# ADB-3020-CDV.net
KiCad netlist of a schematic drawn in EAGLE
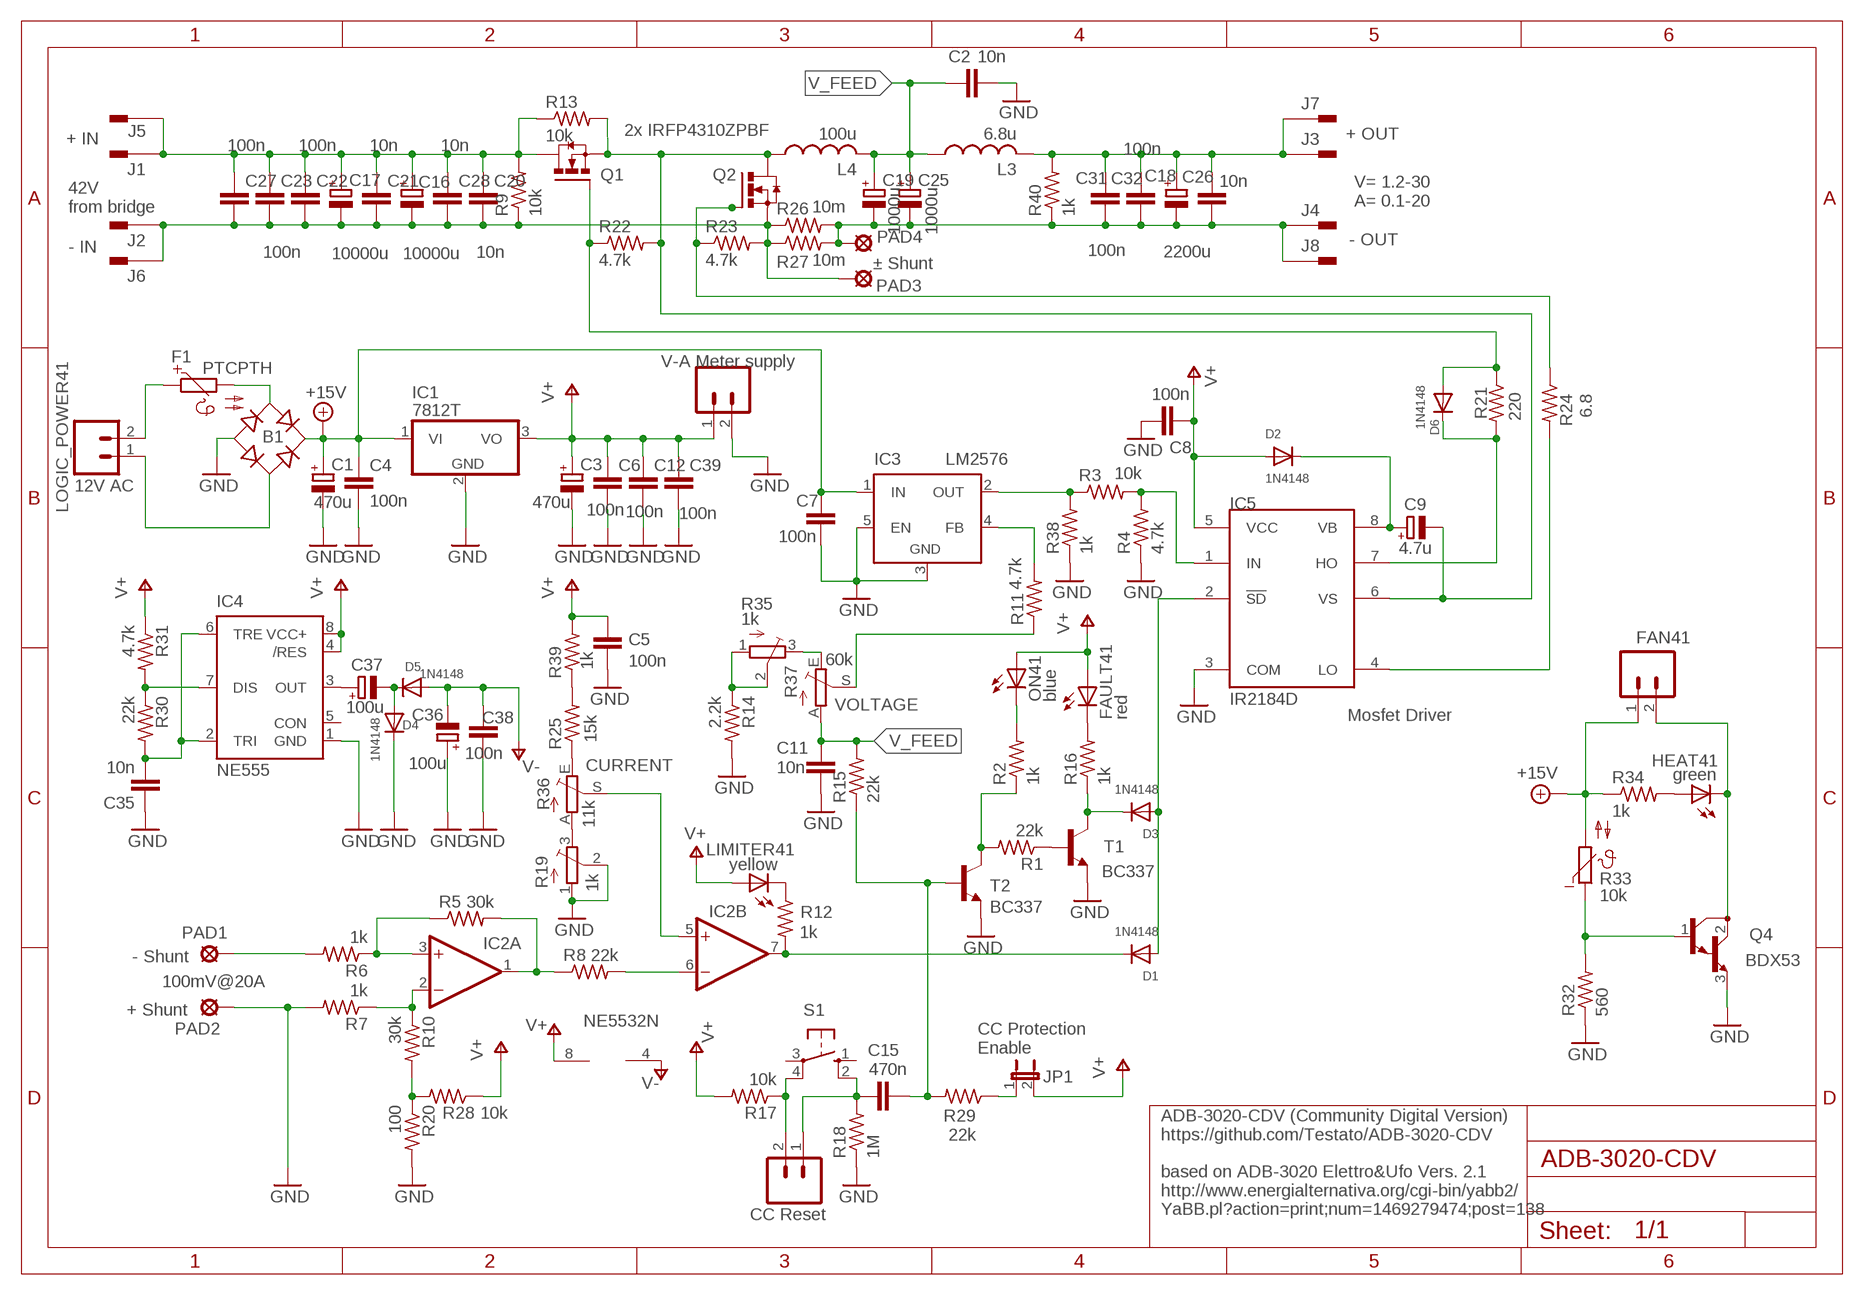
[diagram p0: schematic, sheet 1]

(export (version "E")
  (design (tool "Eeschema 10.0.6"))
  (components
    (comp (ref "B1")
      (value "RECTIFIER-RB1A")
      (footprint "eagle-import:RB1A")
      (libsource (lib "eagle-import") (part "RECTIFIER-RB1A"))
    )
    (comp (ref "C1")
      (value "470u")
      (footprint "eagle-import:E2-5")
      (libsource (lib "eagle-import") (part "CPOL-EUE2-5"))
    )
    (comp (ref "C2")
      (value "10n")
      (footprint "eagle-import:C2.5-2")
      (libsource (lib "eagle-import") (part "C2.5/2"))
    )
    (comp (ref "C3")
      (value "470u")
      (footprint "eagle-import:E2-5")
      (libsource (lib "eagle-import") (part "CPOL-EUE2-5"))
    )
    (comp (ref "C4")
      (value "100n")
      (footprint "eagle-import:C2.5-2")
      (libsource (lib "eagle-import") (part "C2.5/2"))
    )
    (comp (ref "C5")
      (value "100n")
      (footprint "eagle-import:C2.5-2")
      (libsource (lib "eagle-import") (part "C2.5/2"))
    )
    (comp (ref "C6")
      (value "100n")
      (footprint "eagle-import:C2.5-2")
      (libsource (lib "eagle-import") (part "C2.5/2"))
    )
    (comp (ref "C7")
      (value "100n")
      (footprint "eagle-import:C2.5-2")
      (libsource (lib "eagle-import") (part "C2.5/2"))
    )
    (comp (ref "C8")
      (value "100n")
      (footprint "eagle-import:C2.5-2")
      (libsource (lib "eagle-import") (part "C2.5/2"))
    )
    (comp (ref "C9")
      (value "4.7u")
      (footprint "eagle-import:E2-5")
      (libsource (lib "eagle-import") (part "CPOL-EUE2-5"))
    )
    (comp (ref "C11")
      (value "10n")
      (footprint "eagle-import:C2.5-2")
      (libsource (lib "eagle-import") (part "C2.5/2"))
    )
    (comp (ref "C12")
      (value "100n")
      (footprint "eagle-import:C2.5-2")
      (libsource (lib "eagle-import") (part "C2.5/2"))
    )
    (comp (ref "C15")
      (value "470n")
      (footprint "eagle-import:C2.5-2")
      (libsource (lib "eagle-import") (part "C2.5/2"))
    )
    (comp (ref "C16")
      (value "10000u")
      (footprint "eagle-import:E2-5")
      (libsource (lib "eagle-import") (part "CPOL-EUE2-5"))
    )
    (comp (ref "C17")
      (value "10000u")
      (footprint "eagle-import:E2-5")
      (libsource (lib "eagle-import") (part "CPOL-EUE2-5"))
    )
    (comp (ref "C18")
      (value "2200u")
      (footprint "eagle-import:E2-5")
      (libsource (lib "eagle-import") (part "CPOL-EUE2-5"))
    )
    (comp (ref "C19")
      (value "1000u")
      (footprint "eagle-import:E2-5")
      (libsource (lib "eagle-import") (part "CPOL-EUE2-5"))
    )
    (comp (ref "C20")
      (value "10n")
      (footprint "eagle-import:C2.5-2")
      (libsource (lib "eagle-import") (part "C2.5/2"))
    )
    (comp (ref "C21")
      (value "10n")
      (footprint "eagle-import:C2.5-2")
      (libsource (lib "eagle-import") (part "C2.5/2"))
    )
    (comp (ref "C22")
      (value "100n")
      (footprint "eagle-import:C2.5-2")
      (libsource (lib "eagle-import") (part "C2.5/2"))
    )
    (comp (ref "C23")
      (value "100n")
      (footprint "eagle-import:C2.5-2")
      (libsource (lib "eagle-import") (part "C2.5/2"))
    )
    (comp (ref "C25")
      (value "1000u")
      (footprint "eagle-import:E2-5")
      (libsource (lib "eagle-import") (part "CPOL-EUE2-5"))
    )
    (comp (ref "C26")
      (value "10n")
      (footprint "eagle-import:C2.5-2")
      (libsource (lib "eagle-import") (part "C2.5/2"))
    )
    (comp (ref "C27")
      (value "100n")
      (footprint "eagle-import:C2.5-2")
      (libsource (lib "eagle-import") (part "C2.5/2"))
    )
    (comp (ref "C28")
      (value "10n")
      (footprint "eagle-import:C2.5-2")
      (libsource (lib "eagle-import") (part "C2.5/2"))
    )
    (comp (ref "C31")
      (value "100n")
      (footprint "eagle-import:C2.5-2")
      (libsource (lib "eagle-import") (part "C2.5/2"))
    )
    (comp (ref "C32")
      (value "100n")
      (footprint "eagle-import:C2.5-2")
      (libsource (lib "eagle-import") (part "C2.5/2"))
    )
    (comp (ref "C35")
      (value "10n")
      (footprint "eagle-import:C2.5-2")
      (libsource (lib "eagle-import") (part "C2.5/2"))
    )
    (comp (ref "C36")
      (value "100u")
      (footprint "eagle-import:E2-5")
      (libsource (lib "eagle-import") (part "CPOL-EUE2-5"))
    )
    (comp (ref "C37")
      (value "100u")
      (footprint "eagle-import:E2-5")
      (libsource (lib "eagle-import") (part "CPOL-EUE2-5"))
    )
    (comp (ref "C38")
      (value "100n")
      (footprint "eagle-import:C2.5-2")
      (libsource (lib "eagle-import") (part "C2.5/2"))
    )
    (comp (ref "C39")
      (value "100n")
      (footprint "eagle-import:C2.5-2")
      (libsource (lib "eagle-import") (part "C2.5/2"))
    )
    (comp (ref "D1")
      (value "1N4148")
      (footprint "eagle-import:DO-1N4148")
      (libsource (lib "eagle-import") (part "DIODEDO-1N4148"))
    )
    (comp (ref "D2")
      (value "1N4148")
      (footprint "eagle-import:DO-1N4148")
      (libsource (lib "eagle-import") (part "DIODEDO-1N4148"))
    )
    (comp (ref "D3")
      (value "1N4148")
      (footprint "eagle-import:DO-1N4148")
      (libsource (lib "eagle-import") (part "DIODEDO-1N4148"))
    )
    (comp (ref "D4")
      (value "1N4148")
      (footprint "eagle-import:DO-1N4148")
      (libsource (lib "eagle-import") (part "DIODEDO-1N4148"))
    )
    (comp (ref "D5")
      (value "1N4148")
      (footprint "eagle-import:DO-1N4148")
      (libsource (lib "eagle-import") (part "DIODEDO-1N4148"))
    )
    (comp (ref "D6")
      (value "1N4148")
      (footprint "eagle-import:DO-1N4148")
      (libsource (lib "eagle-import") (part "DIODEDO-1N4148"))
    )
    (comp (ref "F1")
      (value "PTCPTH")
      (footprint "eagle-import:P660")
      (libsource (lib "eagle-import") (part "PTC660"))
    )
    (comp (ref "FAN41")
      (value "fan")
      (footprint "eagle-import:02PA")
      (libsource (lib "eagle-import") (part "MA02"))
    )
    (comp (ref "FAULT41")
      (value "red")
      (footprint "eagle-import:LED3MM")
      (libsource (lib "eagle-import") (part "LED3MM"))
    )
    (comp (ref "HEAT41")
      (value "green")
      (footprint "eagle-import:LED3MM")
      (libsource (lib "eagle-import") (part "LED3MM"))
    )
    (comp (ref "IC1")
      (value "7812T")
      (footprint "eagle-import:TO220H")
      (libsource (lib "eagle-import") (part "78T12"))
    )
    (comp (ref "IC2")
      (value "NE5532N")
      (footprint "eagle-import:DIL08")
      (libsource (lib "eagle-import") (part "NE5532N"))
    )
    (comp (ref "IC3")
      (value "LM2576")
      (footprint "eagle-import:TO220-52")
      (libsource (lib "eagle-import") (part "LM2596TH"))
    )
    (comp (ref "IC4")
      (value "NE555")
      (footprint "eagle-import:DIL-08")
      (fields (field (name "MF") "Arrow Electronics") (field (name "MPN") "NE555N"))
      (libsource (lib "eagle-import") (part "NE555"))
    )
    (comp (ref "IC5")
      (value "IR2184D")
      (footprint "eagle-import:DIL08")
      (libsource (lib "eagle-import") (part "IR2184D"))
    )
    (comp (ref "J1")
      (value "+ IN")
      (footprint "eagle-import:F061.040")
      (libsource (lib "eagle-import") (part "PIN2F061.040"))
    )
    (comp (ref "J2")
      (value "- IN")
      (footprint "eagle-import:F061.040")
      (libsource (lib "eagle-import") (part "PIN2F061.040"))
    )
    (comp (ref "J3")
      (value "+ OUT")
      (footprint "eagle-import:F061.040")
      (libsource (lib "eagle-import") (part "PIN2F061.040"))
    )
    (comp (ref "J4")
      (value "PIN2F061.040")
      (footprint "eagle-import:F061.040")
      (libsource (lib "eagle-import") (part "PIN2F061.040"))
    )
    (comp (ref "J5")
      (value "+ IN")
      (footprint "eagle-import:F061.040")
      (libsource (lib "eagle-import") (part "PIN2F061.040"))
    )
    (comp (ref "J6")
      (value "- IN")
      (footprint "eagle-import:F061.040")
      (libsource (lib "eagle-import") (part "PIN2F061.040"))
    )
    (comp (ref "J7")
      (value "PIN2F061.040")
      (footprint "eagle-import:F061.040")
      (libsource (lib "eagle-import") (part "PIN2F061.040"))
    )
    (comp (ref "J8")
      (value "- OUT")
      (footprint "eagle-import:F061.040")
      (libsource (lib "eagle-import") (part "PIN2F061.040"))
    )
    (comp (ref "JP1")
      (value "jp1")
      (footprint "eagle-import:JP1")
      (libsource (lib "eagle-import") (part "JP1E"))
    )
    (comp (ref "L3")
      (value "6.8u")
      (footprint "eagle-import:6000")
      (libsource (lib "eagle-import") (part "L"))
    )
    (comp (ref "L4")
      (value "100u")
      (footprint "eagle-import:6000")
      (libsource (lib "eagle-import") (part "L"))
    )
    (comp (ref "LIMITER41")
      (value "yellow")
      (footprint "eagle-import:LED3MM")
      (libsource (lib "eagle-import") (part "LED3MM"))
    )
    (comp (ref "LOGIC_POWER41")
      (value "12V AC")
      (footprint "eagle-import:02PA")
      (libsource (lib "eagle-import") (part "MA02"))
    )
    (comp (ref "ON41")
      (value "blue")
      (footprint "eagle-import:LED3MM")
      (libsource (lib "eagle-import") (part "LED3MM"))
    )
    (comp (ref "PAD1")
      (value "LSP13")
      (footprint "eagle-import:LSP13")
      (libsource (lib "eagle-import") (part "LSP13"))
    )
    (comp (ref "PAD2")
      (value "LSP13")
      (footprint "eagle-import:LSP13")
      (libsource (lib "eagle-import") (part "LSP13"))
    )
    (comp (ref "PAD3")
      (value "LSP13")
      (footprint "eagle-import:LSP13")
      (libsource (lib "eagle-import") (part "LSP13"))
    )
    (comp (ref "PAD4")
      (value "LSP13")
      (footprint "eagle-import:LSP13")
      (libsource (lib "eagle-import") (part "LSP13"))
    )
    (comp (ref "Q1")
      (value "IRFP240-H")
      (footprint "eagle-import:TO247BH")
      (libsource (lib "eagle-import") (part "IRFP240-H"))
    )
    (comp (ref "Q2")
      (value "IRFP240-H")
      (footprint "eagle-import:TO247BH")
      (libsource (lib "eagle-import") (part "IRFP240-H"))
    )
    (comp (ref "Q4")
      (value "BDX53")
      (footprint "eagle-import:TO220")
      (libsource (lib "eagle-import") (part "BDX53"))
    )
    (comp (ref "R1")
      (value "22k")
      (footprint "eagle-import:0204_5")
      (libsource (lib "eagle-import") (part "R-US_0204/5"))
    )
    (comp (ref "R2")
      (value "1k")
      (footprint "eagle-import:0204_5")
      (libsource (lib "eagle-import") (part "R-US_0204/5"))
    )
    (comp (ref "R3")
      (value "10k")
      (footprint "eagle-import:0204_5")
      (libsource (lib "eagle-import") (part "R-US_0204/5"))
    )
    (comp (ref "R4")
      (value "4.7k")
      (footprint "eagle-import:0204_5")
      (libsource (lib "eagle-import") (part "R-US_0204/5"))
    )
    (comp (ref "R5")
      (value "30k")
      (footprint "eagle-import:0204_5")
      (libsource (lib "eagle-import") (part "R-US_0204/5"))
    )
    (comp (ref "R6")
      (value "1k")
      (footprint "eagle-import:0204_5")
      (libsource (lib "eagle-import") (part "R-US_0204/5"))
    )
    (comp (ref "R7")
      (value "1k")
      (footprint "eagle-import:0204_5")
      (libsource (lib "eagle-import") (part "R-US_0204/5"))
    )
    (comp (ref "R8")
      (value "22k")
      (footprint "eagle-import:0204_5")
      (libsource (lib "eagle-import") (part "R-US_0204/5"))
    )
    (comp (ref "R9")
      (value "10k")
      (footprint "eagle-import:0204_5")
      (libsource (lib "eagle-import") (part "R-US_0204/5"))
    )
    (comp (ref "R10")
      (value "30k")
      (footprint "eagle-import:0204_5")
      (libsource (lib "eagle-import") (part "R-US_0204/5"))
    )
    (comp (ref "R11")
      (value "4.7k")
      (footprint "eagle-import:0204_5")
      (libsource (lib "eagle-import") (part "R-US_0204/5"))
    )
    (comp (ref "R12")
      (value "1k")
      (footprint "eagle-import:0204_5")
      (libsource (lib "eagle-import") (part "R-US_0204/5"))
    )
    (comp (ref "R13")
      (value "10k")
      (footprint "eagle-import:0204_5")
      (libsource (lib "eagle-import") (part "R-US_0204/5"))
    )
    (comp (ref "R14")
      (value "2.2k")
      (footprint "eagle-import:0204_5")
      (libsource (lib "eagle-import") (part "R-US_0204/5"))
    )
    (comp (ref "R15")
      (value "22k")
      (footprint "eagle-import:0204_5")
      (libsource (lib "eagle-import") (part "R-US_0204/5"))
    )
    (comp (ref "R16")
      (value "1k")
      (footprint "eagle-import:0204_5")
      (libsource (lib "eagle-import") (part "R-US_0204/5"))
    )
    (comp (ref "R17")
      (value "10k")
      (footprint "eagle-import:0204_5")
      (libsource (lib "eagle-import") (part "R-US_0204/5"))
    )
    (comp (ref "R18")
      (value "1M")
      (footprint "eagle-import:0204_5")
      (libsource (lib "eagle-import") (part "R-US_0204/5"))
    )
    (comp (ref "R19")
      (value "1k")
      (footprint "eagle-import:TRIM-3386")
      (libsource (lib "eagle-import") (part "TRIMPOT3386"))
    )
    (comp (ref "R20")
      (value "100")
      (footprint "eagle-import:0204_5")
      (libsource (lib "eagle-import") (part "R-US_0204/5"))
    )
    (comp (ref "R21")
      (value "220")
      (footprint "eagle-import:0204_5")
      (libsource (lib "eagle-import") (part "R-US_0204/5"))
    )
    (comp (ref "R22")
      (value "4.7k")
      (footprint "eagle-import:0204_5")
      (libsource (lib "eagle-import") (part "R-US_0204/5"))
    )
    (comp (ref "R23")
      (value "4.7k")
      (footprint "eagle-import:0204_5")
      (libsource (lib "eagle-import") (part "R-US_0204/5"))
    )
    (comp (ref "R24")
      (value "6.8")
      (footprint "eagle-import:0204_5")
      (libsource (lib "eagle-import") (part "R-US_0204/5"))
    )
    (comp (ref "R25")
      (value "15k")
      (footprint "eagle-import:0204_5")
      (libsource (lib "eagle-import") (part "R-US_0204/5"))
    )
    (comp (ref "R26")
      (value "10m")
      (footprint "eagle-import:0204_5")
      (libsource (lib "eagle-import") (part "R-US_0204/5"))
    )
    (comp (ref "R27")
      (value "10m")
      (footprint "eagle-import:0204_5")
      (libsource (lib "eagle-import") (part "R-US_0204/5"))
    )
    (comp (ref "R28")
      (value "10k")
      (footprint "eagle-import:0204_5")
      (libsource (lib "eagle-import") (part "R-US_0204/5"))
    )
    (comp (ref "R29")
      (value "22k")
      (footprint "eagle-import:0204_5")
      (libsource (lib "eagle-import") (part "R-US_0204/5"))
    )
    (comp (ref "R30")
      (value "22k")
      (footprint "eagle-import:0204_5")
      (libsource (lib "eagle-import") (part "R-US_0204/5"))
    )
    (comp (ref "R31")
      (value "4.7k")
      (footprint "eagle-import:0204_5")
      (libsource (lib "eagle-import") (part "R-US_0204/5"))
    )
    (comp (ref "R32")
      (value "560")
      (footprint "eagle-import:0204_5")
      (libsource (lib "eagle-import") (part "R-US_0204/5"))
    )
    (comp (ref "R33")
      (value "10k")
      (footprint "eagle-import:P640")
      (libsource (lib "eagle-import") (part "NTC640"))
    )
    (comp (ref "R34")
      (value "1k")
      (footprint "eagle-import:0204_5")
      (libsource (lib "eagle-import") (part "R-US_0204/5"))
    )
    (comp (ref "R35")
      (value "1k")
      (footprint "eagle-import:TRIM-3386")
      (libsource (lib "eagle-import") (part "TRIMPOT3386"))
    )
    (comp (ref "R36")
      (value "11k")
      (footprint "eagle-import:S64YW")
      (libsource (lib "eagle-import") (part "TRIM_1234-S64YW"))
    )
    (comp (ref "R37")
      (value "60k")
      (footprint "eagle-import:S64YW")
      (libsource (lib "eagle-import") (part "TRIM_1234-S64YW"))
    )
    (comp (ref "R38")
      (value "1k")
      (footprint "eagle-import:0204_5")
      (libsource (lib "eagle-import") (part "R-US_0204/5"))
    )
    (comp (ref "R39")
      (value "1k")
      (footprint "eagle-import:0204_5")
      (libsource (lib "eagle-import") (part "R-US_0204/5"))
    )
    (comp (ref "R40")
      (value "1k")
      (footprint "eagle-import:0204_5")
      (libsource (lib "eagle-import") (part "R-US_0204/5"))
    )
    (comp (ref "RESET41")
      (value "CC Reset")
      (footprint "eagle-import:02PA")
      (libsource (lib "eagle-import") (part "MA02"))
    )
    (comp (ref "S1")
      (value "CC Reset")
      (footprint "eagle-import:B3F-40XX")
      (fields (field (name "MF") "OMRON COMPONENTS USA") (field (name "MPN") "B3F-4000"))
      (libsource (lib "eagle-import") (part "40-XX"))
    )
    (comp (ref "T1")
      (value "BC337")
      (footprint "eagle-import:TO92")
      (libsource (lib "eagle-import") (part "BC337"))
    )
    (comp (ref "T2")
      (value "BC337")
      (footprint "eagle-import:TO92")
      (libsource (lib "eagle-import") (part "BC337"))
    )
    (comp (ref "V-A_METER_SUPPLY41")
      (value "V-A Meter supply")
      (footprint "eagle-import:02PA")
      (libsource (lib "eagle-import") (part "MA02"))
    )
  )
  (nets
    (net (code "1") (name "+15V") (class "Default")
      (node (ref "B1") (pin "+") (pinfunction "+_+") (pintype "passive"))
      (node (ref "C1") (pin "+") (pinfunction "+_+") (pintype "passive"))
      (node (ref "C4") (pin "1") (pinfunction "1_1") (pintype "passive"))
      (node (ref "C7") (pin "1") (pinfunction "1_1") (pintype "passive"))
      (node (ref "FAN41") (pin "1") (pinfunction "1_1") (pintype "passive"))
      (node (ref "IC1") (pin "1") (pinfunction "VI_1") (pintype "input"))
      (node (ref "IC3") (pin "1") (pinfunction "IN_1") (pintype "input"))
      (node (ref "R33") (pin "2") (pinfunction "2_2") (pintype "passive"))
      (node (ref "R34") (pin "1") (pinfunction "1_1") (pintype "passive"))
    )
    (net (code "2") (name "GND") (class "Default")
      (node (ref "B1") (pin "-") (pinfunction "-_-") (pintype "passive"))
      (node (ref "C1") (pin "-") (pinfunction "-_-") (pintype "passive"))
      (node (ref "C11") (pin "2") (pinfunction "2_2") (pintype "passive"))
      (node (ref "C12") (pin "2") (pinfunction "2_2") (pintype "passive"))
      (node (ref "C2") (pin "2") (pinfunction "2_2") (pintype "passive"))
      (node (ref "C3") (pin "-") (pinfunction "-_-") (pintype "passive"))
      (node (ref "C35") (pin "1") (pinfunction "1_1") (pintype "passive"))
      (node (ref "C36") (pin "+") (pinfunction "+_+") (pintype "passive"))
      (node (ref "C38") (pin "1") (pinfunction "1_1") (pintype "passive"))
      (node (ref "C39") (pin "2") (pinfunction "2_2") (pintype "passive"))
      (node (ref "C4") (pin "2") (pinfunction "2_2") (pintype "passive"))
      (node (ref "C5") (pin "1") (pinfunction "1_1") (pintype "passive"))
      (node (ref "C6") (pin "2") (pinfunction "2_2") (pintype "passive"))
      (node (ref "C7") (pin "2") (pinfunction "2_2") (pintype "passive"))
      (node (ref "C8") (pin "2") (pinfunction "2_2") (pintype "passive"))
      (node (ref "D4") (pin "C") (pinfunction "C_C") (pintype "passive"))
      (node (ref "IC1") (pin "2") (pinfunction "GND_2") (pintype "passive"))
      (node (ref "IC3") (pin "3") (pinfunction "GND_3") (pintype "power_in"))
      (node (ref "IC3") (pin "5") (pinfunction "EN_5") (pintype "input"))
      (node (ref "IC4") (pin "1") (pinfunction "GND_1") (pintype "power_in"))
      (node (ref "IC5") (pin "3") (pinfunction "COM_3") (pintype "power_in"))
      (node (ref "PAD2") (pin "MP") (pinfunction "MP_MP") (pintype "passive"))
      (node (ref "Q4") (pin "3") (pinfunction "E_3") (pintype "passive"))
      (node (ref "R14") (pin "2") (pinfunction "2_2") (pintype "passive"))
      (node (ref "R18") (pin "1") (pinfunction "1_1") (pintype "passive"))
      (node (ref "R19") (pin "1") (pinfunction "A_1") (pintype "passive"))
      (node (ref "R19") (pin "2") (pinfunction "S_2") (pintype "passive"))
      (node (ref "R20") (pin "2") (pinfunction "2_2") (pintype "passive"))
      (node (ref "R32") (pin "1") (pinfunction "1_1") (pintype "passive"))
      (node (ref "R38") (pin "1") (pinfunction "1_1") (pintype "passive"))
      (node (ref "R4") (pin "1") (pinfunction "1_1") (pintype "passive"))
      (node (ref "R7") (pin "2") (pinfunction "2_2") (pintype "passive"))
      (node (ref "T1") (pin "1") (pinfunction "E_1") (pintype "passive"))
      (node (ref "T2") (pin "1") (pinfunction "E_1") (pintype "passive"))
      (node (ref "V-A_METER_SUPPLY41") (pin "2") (pinfunction "2_2") (pintype "passive"))
    )
    (net (code "3") (name "Net-(B1-PadAC1)") (class "Default")
      (node (ref "B1") (pin "AC1") (pinfunction "AC1_AC1") (pintype "passive"))
      (node (ref "F1") (pin "2") (pinfunction "2_2") (pintype "passive"))
    )
    (net (code "4") (name "Net-(B1-PadAC2)") (class "Default")
      (node (ref "B1") (pin "AC2") (pinfunction "AC2_AC2") (pintype "passive"))
      (node (ref "LOGIC_POWER41") (pin "1") (pinfunction "1_1") (pintype "passive"))
    )
    (net (code "5") (name "Net-(C16-Pad+)") (class "Default")
      (node (ref "C16") (pin "+") (pinfunction "+_+") (pintype "passive"))
      (node (ref "C17") (pin "+") (pinfunction "+_+") (pintype "passive"))
      (node (ref "C20") (pin "1") (pinfunction "1_1") (pintype "passive"))
      (node (ref "C21") (pin "1") (pinfunction "1_1") (pintype "passive"))
      (node (ref "C22") (pin "1") (pinfunction "1_1") (pintype "passive"))
      (node (ref "C23") (pin "1") (pinfunction "1_1") (pintype "passive"))
      (node (ref "C27") (pin "1") (pinfunction "1_1") (pintype "passive"))
      (node (ref "C28") (pin "1") (pinfunction "1_1") (pintype "passive"))
      (node (ref "J1") (pin "A1") (pinfunction "1_A1") (pintype "passive"))
      (node (ref "J1") (pin "A2") (pinfunction "1_A2") (pintype "passive"))
      (node (ref "J5") (pin "A1") (pinfunction "1_A1") (pintype "passive"))
      (node (ref "J5") (pin "A2") (pinfunction "1_A2") (pintype "passive"))
      (node (ref "Q1") (pin "D") (pinfunction "D_D") (pintype "passive"))
      (node (ref "R13") (pin "1") (pinfunction "1_1") (pintype "passive"))
      (node (ref "R9") (pin "2") (pinfunction "2_2") (pintype "passive"))
    )
    (net (code "6") (name "Net-(C16-Pad-)") (class "Default")
      (node (ref "C16") (pin "-") (pinfunction "-_-") (pintype "passive"))
      (node (ref "C17") (pin "-") (pinfunction "-_-") (pintype "passive"))
      (node (ref "C20") (pin "2") (pinfunction "2_2") (pintype "passive"))
      (node (ref "C21") (pin "2") (pinfunction "2_2") (pintype "passive"))
      (node (ref "C22") (pin "2") (pinfunction "2_2") (pintype "passive"))
      (node (ref "C23") (pin "2") (pinfunction "2_2") (pintype "passive"))
      (node (ref "C27") (pin "2") (pinfunction "2_2") (pintype "passive"))
      (node (ref "C28") (pin "2") (pinfunction "2_2") (pintype "passive"))
      (node (ref "J2") (pin "A1") (pinfunction "1_A1") (pintype "passive"))
      (node (ref "J2") (pin "A2") (pinfunction "1_A2") (pintype "passive"))
      (node (ref "J6") (pin "A1") (pinfunction "1_A1") (pintype "passive"))
      (node (ref "J6") (pin "A2") (pinfunction "1_A2") (pintype "passive"))
      (node (ref "PAD3") (pin "MP") (pinfunction "MP_MP") (pintype "passive"))
      (node (ref "Q2") (pin "S") (pinfunction "S_S") (pintype "passive"))
      (node (ref "R23") (pin "2") (pinfunction "2_2") (pintype "passive"))
      (node (ref "R26") (pin "1") (pinfunction "1_1") (pintype "passive"))
      (node (ref "R27") (pin "1") (pinfunction "1_1") (pintype "passive"))
      (node (ref "R9") (pin "1") (pinfunction "1_1") (pintype "passive"))
    )
    (net (code "7") (name "Net-(C18-Pad+)") (class "Default")
      (node (ref "C18") (pin "+") (pinfunction "+_+") (pintype "passive"))
      (node (ref "C26") (pin "1") (pinfunction "1_1") (pintype "passive"))
      (node (ref "C31") (pin "1") (pinfunction "1_1") (pintype "passive"))
      (node (ref "C32") (pin "1") (pinfunction "1_1") (pintype "passive"))
      (node (ref "J3") (pin "A1") (pinfunction "1_A1") (pintype "passive"))
      (node (ref "J3") (pin "A2") (pinfunction "1_A2") (pintype "passive"))
      (node (ref "J7") (pin "A1") (pinfunction "1_A1") (pintype "passive"))
      (node (ref "J7") (pin "A2") (pinfunction "1_A2") (pintype "passive"))
      (node (ref "L3") (pin "2") (pinfunction "2_2") (pintype "passive"))
      (node (ref "R40") (pin "2") (pinfunction "2_2") (pintype "passive"))
    )
    (net (code "8") (name "Net-(C18-Pad-)") (class "Default")
      (node (ref "C18") (pin "-") (pinfunction "-_-") (pintype "passive"))
      (node (ref "C19") (pin "-") (pinfunction "-_-") (pintype "passive"))
      (node (ref "C25") (pin "-") (pinfunction "-_-") (pintype "passive"))
      (node (ref "C26") (pin "2") (pinfunction "2_2") (pintype "passive"))
      (node (ref "C31") (pin "2") (pinfunction "2_2") (pintype "passive"))
      (node (ref "C32") (pin "2") (pinfunction "2_2") (pintype "passive"))
      (node (ref "J4") (pin "A1") (pinfunction "1_A1") (pintype "passive"))
      (node (ref "J4") (pin "A2") (pinfunction "1_A2") (pintype "passive"))
      (node (ref "J8") (pin "A1") (pinfunction "1_A1") (pintype "passive"))
      (node (ref "J8") (pin "A2") (pinfunction "1_A2") (pintype "passive"))
      (node (ref "PAD4") (pin "MP") (pinfunction "MP_MP") (pintype "passive"))
      (node (ref "R26") (pin "2") (pinfunction "2_2") (pintype "passive"))
      (node (ref "R27") (pin "2") (pinfunction "2_2") (pintype "passive"))
      (node (ref "R40") (pin "1") (pinfunction "1_1") (pintype "passive"))
    )
    (net (code "9") (name "Net-(C37-Pad-)") (class "Default")
      (node (ref "C37") (pin "-") (pinfunction "-_-") (pintype "passive"))
      (node (ref "D4") (pin "A") (pinfunction "A_A") (pintype "passive"))
      (node (ref "D5") (pin "C") (pinfunction "C_C") (pintype "passive"))
    )
    (net (code "10") (name "Net-(D6-PadA)") (class "Default")
      (node (ref "D6") (pin "A") (pinfunction "A_A") (pintype "passive"))
      (node (ref "Q1") (pin "G") (pinfunction "G_G") (pintype "passive"))
      (node (ref "R21") (pin "1") (pinfunction "1_1") (pintype "passive"))
      (node (ref "R22") (pin "1") (pinfunction "1_1") (pintype "passive"))
    )
    (net (code "11") (name "Net-(F1-Pad1)") (class "Default")
      (node (ref "F1") (pin "1") (pinfunction "1_1") (pintype "passive"))
      (node (ref "LOGIC_POWER41") (pin "2") (pinfunction "2_2") (pintype "passive"))
    )
    (net (code "12") (name "Net-(FAULT41-C)") (class "Default")
      (node (ref "FAULT41") (pin "K") (pinfunction "C_K") (pintype "passive"))
      (node (ref "R16") (pin "2") (pinfunction "2_2") (pintype "passive"))
    )
    (net (code "13") (name "Net-(HEAT41-C)") (class "Default")
      (node (ref "FAN41") (pin "2") (pinfunction "2_2") (pintype "passive"))
      (node (ref "HEAT41") (pin "K") (pinfunction "C_K") (pintype "passive"))
      (node (ref "Q4") (pin "2") (pinfunction "C_2") (pintype "passive"))
    )
    (net (code "14") (name "Net-(HEAT41-PadA)") (class "Default")
      (node (ref "HEAT41") (pin "A") (pinfunction "A_A") (pintype "passive"))
      (node (ref "R34") (pin "2") (pinfunction "2_2") (pintype "passive"))
    )
    (net (code "15") (name "Net-(IC2A-+IN)") (class "Default")
      (node (ref "IC2") (pin "3") (pinfunction "+IN_3") (pintype "input"))
      (node (ref "R5") (pin "1") (pinfunction "1_1") (pintype "passive"))
      (node (ref "R6") (pin "1") (pinfunction "1_1") (pintype "passive"))
    )
    (net (code "16") (name "Net-(IC2A--IN)") (class "Default")
      (node (ref "IC2") (pin "2") (pinfunction "-IN_2") (pintype "input"))
      (node (ref "R10") (pin "1") (pinfunction "1_1") (pintype "passive"))
      (node (ref "R7") (pin "1") (pinfunction "1_1") (pintype "passive"))
    )
    (net (code "17") (name "Net-(IC2A-OUT)") (class "Default")
      (node (ref "IC2") (pin "1") (pinfunction "OUT_1") (pintype "output"))
      (node (ref "R5") (pin "2") (pinfunction "2_2") (pintype "passive"))
      (node (ref "R8") (pin "1") (pinfunction "1_1") (pintype "passive"))
    )
    (net (code "18") (name "Net-(IC2B-+IN)") (class "Default")
      (node (ref "IC2") (pin "5") (pinfunction "+IN_5") (pintype "input"))
      (node (ref "R36") (pin "S") (pinfunction "S_S") (pintype "passive"))
    )
    (net (code "19") (name "Net-(IC2B--IN)") (class "Default")
      (node (ref "IC2") (pin "6") (pinfunction "-IN_6") (pintype "input"))
      (node (ref "R8") (pin "2") (pinfunction "2_2") (pintype "passive"))
    )
    (net (code "20") (name "Net-(IC2B-OUT)") (class "Default")
      (node (ref "D1") (pin "C") (pinfunction "C_C") (pintype "passive"))
      (node (ref "IC2") (pin "7") (pinfunction "OUT_7") (pintype "output"))
      (node (ref "R12") (pin "2") (pinfunction "2_2") (pintype "passive"))
    )
    (net (code "21") (name "Net-(IC3-FB)") (class "Default")
      (node (ref "IC3") (pin "4") (pinfunction "FB_4") (pintype "input"))
      (node (ref "R11") (pin "2") (pinfunction "2_2") (pintype "passive"))
    )
    (net (code "22") (name "Net-(IC3-OUT)") (class "Default")
      (node (ref "IC3") (pin "2") (pinfunction "OUT_2") (pintype "output"))
      (node (ref "R3") (pin "1") (pinfunction "1_1") (pintype "passive"))
      (node (ref "R38") (pin "2") (pinfunction "2_2") (pintype "passive"))
    )
    (net (code "23") (name "Net-(IC4-DIS)") (class "Default")
      (node (ref "IC4") (pin "7") (pinfunction "DIS_7") (pintype "input"))
      (node (ref "R30") (pin "1") (pinfunction "1_1") (pintype "passive"))
      (node (ref "R31") (pin "2") (pinfunction "2_2") (pintype "passive"))
    )
    (net (code "24") (name "Net-(IC4-OUT)") (class "Default")
      (node (ref "C37") (pin "+") (pinfunction "+_+") (pintype "passive"))
      (node (ref "IC4") (pin "3") (pinfunction "OUT_3") (pintype "output"))
    )
    (net (code "25") (name "Net-(IC4-TRE)") (class "Default")
      (node (ref "C35") (pin "2") (pinfunction "2_2") (pintype "passive"))
      (node (ref "IC4") (pin "2") (pinfunction "TRI_2") (pintype "input"))
      (node (ref "IC4") (pin "6") (pinfunction "TRE_6") (pintype "input"))
      (node (ref "R30") (pin "2") (pinfunction "2_2") (pintype "passive"))
    )
    (net (code "26") (name "Net-(IC5-HO)") (class "Default")
      (node (ref "D6") (pin "C") (pinfunction "C_C") (pintype "passive"))
      (node (ref "IC5") (pin "7") (pinfunction "HO_7") (pintype "output"))
      (node (ref "R21") (pin "2") (pinfunction "2_2") (pintype "passive"))
    )
    (net (code "27") (name "Net-(IC5-IN)") (class "Default")
      (node (ref "IC5") (pin "1") (pinfunction "IN_1") (pintype "input"))
      (node (ref "R3") (pin "2") (pinfunction "2_2") (pintype "passive"))
      (node (ref "R4") (pin "2") (pinfunction "2_2") (pintype "passive"))
    )
    (net (code "28") (name "Net-(IC5-LO)") (class "Default")
      (node (ref "IC5") (pin "4") (pinfunction "LO_4") (pintype "output"))
      (node (ref "R24") (pin "2") (pinfunction "2_2") (pintype "passive"))
    )
    (net (code "29") (name "Net-(IC5-VB)") (class "Default")
      (node (ref "C9") (pin "+") (pinfunction "+_+") (pintype "passive"))
      (node (ref "D2") (pin "C") (pinfunction "C_C") (pintype "passive"))
      (node (ref "IC5") (pin "8") (pinfunction "VB_8") (pintype "power_in"))
    )
    (net (code "30") (name "Net-(IC5-VS)") (class "Default")
      (node (ref "C9") (pin "-") (pinfunction "-_-") (pintype "passive"))
      (node (ref "IC5") (pin "6") (pinfunction "VS_6") (pintype "power_in"))
      (node (ref "L4") (pin "1") (pinfunction "1_1") (pintype "passive"))
      (node (ref "Q1") (pin "S") (pinfunction "S_S") (pintype "passive"))
      (node (ref "Q2") (pin "D") (pinfunction "D_D") (pintype "passive"))
      (node (ref "R13") (pin "2") (pinfunction "2_2") (pintype "passive"))
      (node (ref "R22") (pin "2") (pinfunction "2_2") (pintype "passive"))
    )
    (net (code "31") (name "Net-(IC5-~{SD})") (class "Default")
      (node (ref "D1") (pin "A") (pinfunction "A_A") (pintype "passive"))
      (node (ref "D3") (pin "A") (pinfunction "A_A") (pintype "passive"))
      (node (ref "IC5") (pin "2") (pinfunction "~{SD}_2") (pintype "input"))
    )
    (net (code "32") (name "Net-(JP1-Pad1)") (class "Default")
      (node (ref "JP1") (pin "1") (pinfunction "1_1") (pintype "passive"))
      (node (ref "R29") (pin "1") (pinfunction "1_1") (pintype "passive"))
    )
    (net (code "33") (name "Net-(LIMITER41-C)") (class "Default")
      (node (ref "LIMITER41") (pin "K") (pinfunction "C_K") (pintype "passive"))
      (node (ref "R12") (pin "1") (pinfunction "1_1") (pintype "passive"))
    )
    (net (code "34") (name "Net-(ON41-C)") (class "Default")
      (node (ref "ON41") (pin "K") (pinfunction "C_K") (pintype "passive"))
      (node (ref "R2") (pin "2") (pinfunction "2_2") (pintype "passive"))
    )
    (net (code "35") (name "Net-(PAD1-PadMP)") (class "Default")
      (node (ref "PAD1") (pin "MP") (pinfunction "MP_MP") (pintype "passive"))
      (node (ref "R6") (pin "2") (pinfunction "2_2") (pintype "passive"))
    )
    (net (code "36") (name "Net-(Q2-PadG)") (class "Default")
      (node (ref "Q2") (pin "G") (pinfunction "G_G") (pintype "passive"))
      (node (ref "R23") (pin "1") (pinfunction "1_1") (pintype "passive"))
      (node (ref "R24") (pin "1") (pinfunction "1_1") (pintype "passive"))
    )
    (net (code "37") (name "Net-(Q4-B)") (class "Default")
      (node (ref "Q4") (pin "1") (pinfunction "B_1") (pintype "passive"))
      (node (ref "R32") (pin "2") (pinfunction "2_2") (pintype "passive"))
      (node (ref "R33") (pin "1") (pinfunction "1_1") (pintype "passive"))
    )
    (net (code "38") (name "Net-(R10-Pad2)") (class "Default")
      (node (ref "R10") (pin "2") (pinfunction "2_2") (pintype "passive"))
      (node (ref "R20") (pin "1") (pinfunction "1_1") (pintype "passive"))
      (node (ref "R28") (pin "2") (pinfunction "2_2") (pintype "passive"))
    )
    (net (code "39") (name "Net-(R11-Pad1)") (class "Default")
      (node (ref "R11") (pin "1") (pinfunction "1_1") (pintype "passive"))
      (node (ref "R37") (pin "S") (pinfunction "S_S") (pintype "passive"))
    )
    (net (code "40") (name "Net-(R19-E)") (class "Default")
      (node (ref "R19") (pin "3") (pinfunction "E_3") (pintype "passive"))
      (node (ref "R36") (pin "A") (pinfunction "A_A") (pintype "passive"))
    )
    (net (code "41") (name "Net-(R25-Pad1)") (class "Default")
      (node (ref "R25") (pin "1") (pinfunction "1_1") (pintype "passive"))
      (node (ref "R36") (pin "E") (pinfunction "E_E") (pintype "passive"))
    )
    (net (code "42") (name "Net-(R25-Pad2)") (class "Default")
      (node (ref "R25") (pin "2") (pinfunction "2_2") (pintype "passive"))
      (node (ref "R39") (pin "1") (pinfunction "1_1") (pintype "passive"))
    )
    (net (code "43") (name "Net-(R35-A)") (class "Default")
      (node (ref "R14") (pin "1") (pinfunction "1_1") (pintype "passive"))
      (node (ref "R35") (pin "1") (pinfunction "A_1") (pintype "passive"))
      (node (ref "R35") (pin "2") (pinfunction "S_2") (pintype "passive"))
    )
    (net (code "44") (name "Net-(R35-E)") (class "Default")
      (node (ref "R35") (pin "3") (pinfunction "E_3") (pintype "passive"))
      (node (ref "R37") (pin "E") (pinfunction "E_E") (pintype "passive"))
    )
    (net (code "45") (name "Net-(S1-P1)") (class "Default")
      (node (ref "R17") (pin "1") (pinfunction "1_1") (pintype "passive"))
      (node (ref "RESET41") (pin "2") (pinfunction "2_2") (pintype "passive"))
      (node (ref "S1") (pin "4") (pinfunction "P1_4") (pintype "passive"))
    )
    (net (code "46") (name "Net-(S1-S1)") (class "Default")
      (node (ref "C15") (pin "1") (pinfunction "1_1") (pintype "passive"))
      (node (ref "R18") (pin "2") (pinfunction "2_2") (pintype "passive"))
      (node (ref "RESET41") (pin "1") (pinfunction "1_1") (pintype "passive"))
      (node (ref "S1") (pin "2") (pinfunction "S1_2") (pintype "passive"))
    )
    (net (code "47") (name "Net-(T1-B)") (class "Default")
      (node (ref "R1") (pin "1") (pinfunction "1_1") (pintype "passive"))
      (node (ref "T1") (pin "2") (pinfunction "B_2") (pintype "passive"))
    )
    (net (code "48") (name "Net-(T1-C)") (class "Default")
      (node (ref "D3") (pin "C") (pinfunction "C_C") (pintype "passive"))
      (node (ref "R16") (pin "1") (pinfunction "1_1") (pintype "passive"))
      (node (ref "T1") (pin "3") (pinfunction "C_3") (pintype "passive"))
    )
    (net (code "49") (name "Net-(T2-B)") (class "Default")
      (node (ref "C15") (pin "2") (pinfunction "2_2") (pintype "passive"))
      (node (ref "R15") (pin "1") (pinfunction "1_1") (pintype "passive"))
      (node (ref "R29") (pin "2") (pinfunction "2_2") (pintype "passive"))
      (node (ref "T2") (pin "2") (pinfunction "B_2") (pintype "passive"))
    )
    (net (code "50") (name "Net-(T2-C)") (class "Default")
      (node (ref "R1") (pin "2") (pinfunction "2_2") (pintype "passive"))
      (node (ref "R2") (pin "1") (pinfunction "1_1") (pintype "passive"))
      (node (ref "T2") (pin "3") (pinfunction "C_3") (pintype "passive"))
    )
    (net (code "51") (name "V+") (class "Default")
      (node (ref "C12") (pin "1") (pinfunction "1_1") (pintype "passive"))
      (node (ref "C3") (pin "+") (pinfunction "+_+") (pintype "passive"))
      (node (ref "C39") (pin "1") (pinfunction "1_1") (pintype "passive"))
      (node (ref "C5") (pin "2") (pinfunction "2_2") (pintype "passive"))
      (node (ref "C6") (pin "1") (pinfunction "1_1") (pintype "passive"))
      (node (ref "C8") (pin "1") (pinfunction "1_1") (pintype "passive"))
      (node (ref "D2") (pin "A") (pinfunction "A_A") (pintype "passive"))
      (node (ref "FAULT41") (pin "A") (pinfunction "A_A") (pintype "passive"))
      (node (ref "IC1") (pin "3") (pinfunction "VO_3") (pintype "passive"))
      (node (ref "IC2") (pin "8") (pinfunction "V+_8") (pintype "power_in"))
      (node (ref "IC4") (pin "4") (pinfunction "/RES_4") (pintype "input"))
      (node (ref "IC4") (pin "8") (pinfunction "VCC+_8") (pintype "power_in"))
      (node (ref "IC5") (pin "5") (pinfunction "VCC_5") (pintype "power_in"))
      (node (ref "JP1") (pin "2") (pinfunction "2_2") (pintype "passive"))
      (node (ref "LIMITER41") (pin "A") (pinfunction "A_A") (pintype "passive"))
      (node (ref "ON41") (pin "A") (pinfunction "A_A") (pintype "passive"))
      (node (ref "R17") (pin "2") (pinfunction "2_2") (pintype "passive"))
      (node (ref "R28") (pin "1") (pinfunction "1_1") (pintype "passive"))
      (node (ref "R31") (pin "1") (pinfunction "1_1") (pintype "passive"))
      (node (ref "R39") (pin "2") (pinfunction "2_2") (pintype "passive"))
      (node (ref "V-A_METER_SUPPLY41") (pin "1") (pinfunction "1_1") (pintype "passive"))
    )
    (net (code "52") (name "V-") (class "Default")
      (node (ref "C36") (pin "-") (pinfunction "-_-") (pintype "passive"))
      (node (ref "C38") (pin "2") (pinfunction "2_2") (pintype "passive"))
      (node (ref "D5") (pin "A") (pinfunction "A_A") (pintype "passive"))
      (node (ref "IC2") (pin "4") (pinfunction "V-_4") (pintype "power_in"))
    )
    (net (code "53") (name "V_FEED") (class "Default")
      (node (ref "C11") (pin "1") (pinfunction "1_1") (pintype "passive"))
      (node (ref "C19") (pin "+") (pinfunction "+_+") (pintype "passive"))
      (node (ref "C2") (pin "1") (pinfunction "1_1") (pintype "passive"))
      (node (ref "C25") (pin "+") (pinfunction "+_+") (pintype "passive"))
      (node (ref "L3") (pin "1") (pinfunction "1_1") (pintype "passive"))
      (node (ref "L4") (pin "2") (pinfunction "2_2") (pintype "passive"))
      (node (ref "R15") (pin "2") (pinfunction "2_2") (pintype "passive"))
      (node (ref "R37") (pin "A") (pinfunction "A_A") (pintype "passive"))
    )
    (net (code "54") (name "unconnected-(IC4-CON-Pad5)") (class "Default")
      (node (ref "IC4") (pin "5") (pinfunction "CON_5") (pintype "input"))
    )
    (net (code "55") (name "unconnected-(R36-S-PadS@1)") (class "Default")
      (node (ref "R36") (pin "S@1") (pinfunction "S_S@1") (pintype "passive"))
    )
    (net (code "56") (name "unconnected-(R37-S-PadS@1)") (class "Default")
      (node (ref "R37") (pin "S@1") (pinfunction "S_S@1") (pintype "passive"))
    )
    (net (code "57") (name "unconnected-(S1-P-Pad3)") (class "Default")
      (node (ref "S1") (pin "3") (pinfunction "P_3") (pintype "passive"))
    )
    (net (code "58") (name "unconnected-(S1-S-Pad1)") (class "Default")
      (node (ref "S1") (pin "1") (pinfunction "S_1") (pintype "passive"))
    )
  )
)
